# ADC_FE4PID.net
KiCad netlist of a schematic drawn in Altium Designer
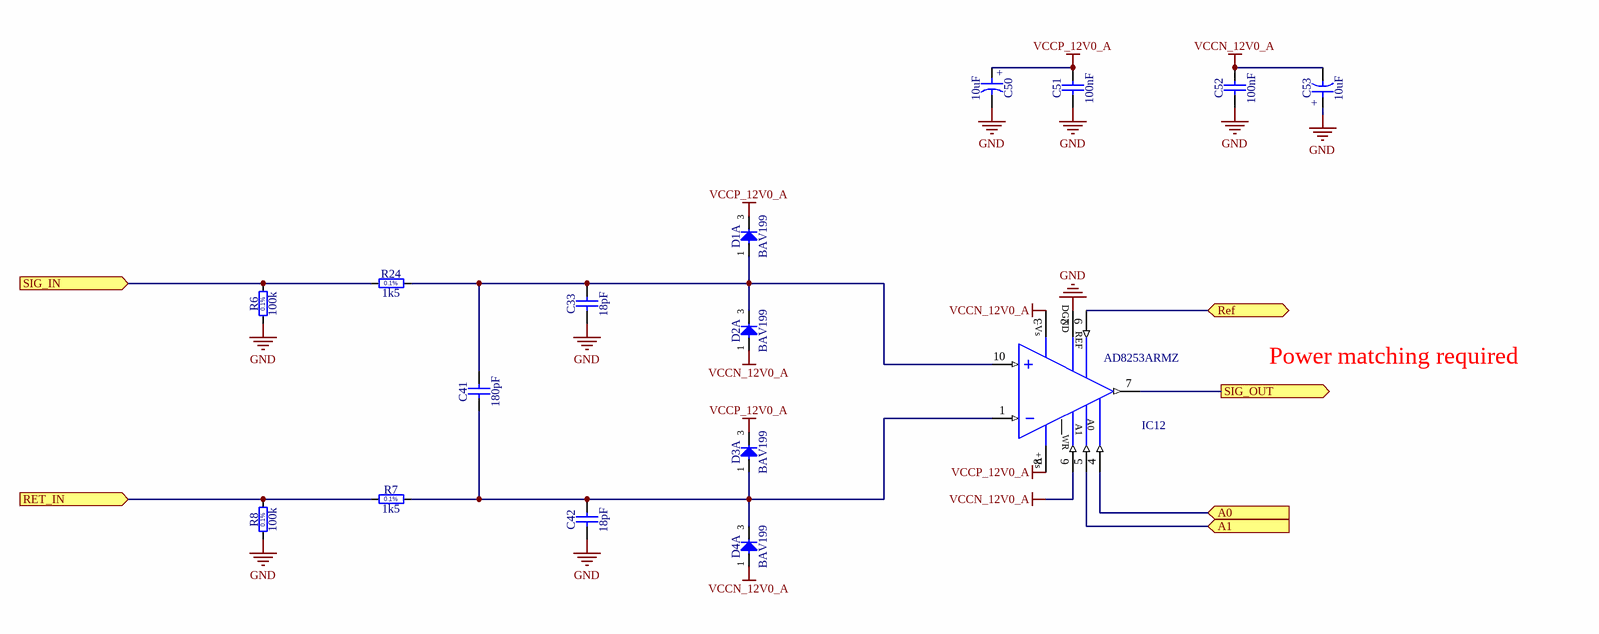
[diagram p0: ADC_FE4PID.SchDoc]

(export (version "E")
  (design (tool "Eeschema 10.0.6"))
  (components
    (comp (ref "C33")
      (value "18pF")
      (footprint "CAPC1005X55N")
      (description "Non-polarised capacitor")
      (fields
        (field (name "PART NUMBER") "CC0402_18PF_50V_5%_C0G")
        (field (name "VOLTAGE") "50V")
        (field (name "AUTHOR") "CERN DEM JLC")
      )
      (libsource (lib "Capacitors") (part "Capacitor - non polarized"))
    )
    (comp (ref "C41")
      (value "180pF")
      (footprint "CAPC1608X87N")
      (description "Non-polarised capacitor")
      (fields
        (field (name "PART NUMBER") "CC0603_180PF_50V_5%_NP0")
        (field (name "VOLTAGE") "50V")
        (field (name "AUTHOR") "CERN DEM JLC")
      )
      (libsource (lib "Capacitors") (part "Capacitor - non polarized"))
    )
    (comp (ref "C42")
      (value "18pF")
      (footprint "CAPC1005X55N")
      (description "Non-polarised capacitor")
      (fields
        (field (name "PART NUMBER") "CC0402_18PF_50V_5%_C0G")
        (field (name "VOLTAGE") "50V")
        (field (name "AUTHOR") "CERN DEM JLC")
      )
      (libsource (lib "Capacitors") (part "Capacitor - non polarized"))
    )
    (comp (ref "C50")
      (value "10uF")
      (footprint "CAPMP3216X180N")
      (description "Polarised capacitor")
      (fields
        (field (name "PART NUMBER") "CTE3216-18_10UF_10V_10%_LESR1800")
        (field (name "VOLTAGE") "10V")
        (field (name "AUTHOR") "CERN DEM JLC")
      )
      (libsource (lib "Capacitors") (part "Capacitor - polarized"))
    )
    (comp (ref "C51")
      (value "100nF")
      (footprint "CAPC1005X55N")
      (description "Non-polarised capacitor")
      (fields
        (field (name "PART NUMBER") "CC0402_100NF_16V_10%_X7R")
        (field (name "VOLTAGE") "16V")
        (field (name "AUTHOR") "CERN DEM JLC")
      )
      (libsource (lib "Capacitors") (part "Capacitor - non polarized"))
    )
    (comp (ref "C52")
      (value "100nF")
      (footprint "CAPC1005X55N")
      (description "Non-polarised capacitor")
      (fields
        (field (name "PART NUMBER") "CC0402_100NF_16V_10%_X7R")
        (field (name "VOLTAGE") "16V")
        (field (name "AUTHOR") "CERN DEM JLC")
      )
      (libsource (lib "Capacitors") (part "Capacitor - non polarized"))
    )
    (comp (ref "C53")
      (value "10uF")
      (footprint "CAPMP3216X180N")
      (description "Polarised capacitor")
      (fields
        (field (name "PART NUMBER") "CTE3216-18_10UF_10V_10%_LESR1800")
        (field (name "VOLTAGE") "10V")
        (field (name "AUTHOR") "CERN DEM JLC")
      )
      (libsource (lib "Capacitors") (part "Capacitor - polarized"))
    )
    (comp (ref "D1")
      (value "BAV199")
      (footprint "SOT95P240X110-3N")
      (description "Serial Diode")
      (fields
        (field (name "VOLTAGE") "75V")
        (field (name "POWER") "250mW")
        (field (name "AUTHOR") "CERN DEM JMW")
      )
      (libsource (lib "ICs And Semiconductors") (part "Diode x2 A1C3_A3C2"))
    )
    (comp (ref "D2")
      (value "BAV199")
      (footprint "SOT95P240X110-3N")
      (description "Serial Diode")
      (fields
        (field (name "VOLTAGE") "75V")
        (field (name "POWER") "250mW")
        (field (name "AUTHOR") "CERN DEM JMW")
      )
      (libsource (lib "ICs And Semiconductors") (part "Diode x2 A1C3_A3C2"))
    )
    (comp (ref "D3")
      (value "BAV199")
      (footprint "SOT95P240X110-3N")
      (description "Serial Diode")
      (fields
        (field (name "VOLTAGE") "75V")
        (field (name "POWER") "250mW")
        (field (name "AUTHOR") "CERN DEM JMW")
      )
      (libsource (lib "ICs And Semiconductors") (part "Diode x2 A1C3_A3C2"))
    )
    (comp (ref "D4")
      (value "BAV199")
      (footprint "SOT95P240X110-3N")
      (description "Serial Diode")
      (fields
        (field (name "VOLTAGE") "75V")
        (field (name "POWER") "250mW")
        (field (name "AUTHOR") "CERN DEM JMW")
      )
      (libsource (lib "ICs And Semiconductors") (part "Diode x2 A1C3_A3C2"))
    )
    (comp (ref "IC12")
      (value "AD8253ARMZ")
      (footprint "SOP50P490X110-10N")
      (description "10MHz, 20V/us, G= 1, 10, 100, 1000 iCMOS Programmable Gain Instrumentation Amplifier")
      (fields (field (name "MANUFACTURER") "ANALOG DEVICES") (field (name "AUTHOR") "CERN DEM JLC"))
      (libsource (lib "ICs And Semiconductors") (part "AD8253"))
    )
    (comp (ref "R6")
      (value "100k")
      (footprint "RESC1005X35N")
      (description "Resistor - 0.1%")
      (fields
        (field (name "PART NUMBER") "R0402_100K_0.1%_0.063W_25PPM")
        (field (name "POWER") "0.063W")
        (field (name "AUTHOR") "CERN DEM JMW")
      )
      (libsource (lib "Resistors") (part "Resistor - 0.1%"))
    )
    (comp (ref "R7")
      (value "1k5")
      (footprint "RESC1608X55N")
      (description "Resistor - 0.1%")
      (fields
        (field (name "PART NUMBER") "R0603_1K5_0.1%_0.063W_10PPM")
        (field (name "POWER") "0.063W")
        (field (name "AUTHOR") "CERN DEM JLC")
      )
      (libsource (lib "Resistors") (part "Resistor - 0.1%"))
    )
    (comp (ref "R8")
      (value "100k")
      (footprint "RESC1005X35N")
      (description "Resistor - 0.1%")
      (fields
        (field (name "PART NUMBER") "R0402_100K_0.1%_0.063W_25PPM")
        (field (name "POWER") "0.063W")
        (field (name "AUTHOR") "CERN DEM JMW")
      )
      (libsource (lib "Resistors") (part "Resistor - 0.1%"))
    )
    (comp (ref "R24")
      (value "1k5")
      (footprint "RESC1608X55N")
      (description "Resistor - 0.1%")
      (fields
        (field (name "PART NUMBER") "R0603_1K5_0.1%_0.063W_10PPM")
        (field (name "POWER") "0.063W")
        (field (name "AUTHOR") "CERN DEM JLC")
      )
      (libsource (lib "Resistors") (part "Resistor - 0.1%"))
    )
  )
  (nets
    (net (code "1") (name "/A0") (class "Default")
      (node (ref "IC12") (pin "4") (pinfunction "A0_4") (pintype "input"))
    )
    (net (code "2") (name "/A1") (class "Default")
      (node (ref "IC12") (pin "5") (pinfunction "A1_5") (pintype "input"))
    )
    (net (code "3") (name "/RET_IN") (class "Default")
      (node (ref "R7") (pin "1") (pinfunction "1_1") (pintype "passive"))
      (node (ref "R8") (pin "2") (pinfunction "2_2") (pintype "passive"))
    )
    (net (code "4") (name "/Ref") (class "Default")
      (node (ref "IC12") (pin "9") (pinfunction "REF_9") (pintype "input"))
    )
    (net (code "5") (name "/SIG_IN") (class "Default")
      (node (ref "R24") (pin "1") (pinfunction "1_1") (pintype "passive"))
      (node (ref "R6") (pin "2") (pinfunction "2_2") (pintype "passive"))
    )
    (net (code "6") (name "/SIG_OUT") (class "Default")
      (node (ref "IC12") (pin "7") (pinfunction "OUT_7") (pintype "output"))
    )
    (net (code "7") (name "GND") (class "Default")
      (node (ref "C33") (pin "1") (pinfunction "1_1") (pintype "passive"))
      (node (ref "C42") (pin "1") (pinfunction "1_1") (pintype "passive"))
      (node (ref "C50") (pin "2") (pinfunction "2_2") (pintype "passive"))
      (node (ref "C51") (pin "1") (pinfunction "1_1") (pintype "passive"))
      (node (ref "C52") (pin "1") (pinfunction "1_1") (pintype "passive"))
      (node (ref "C53") (pin "1") (pinfunction "1_1") (pintype "passive"))
      (node (ref "IC12") (pin "2") (pinfunction "DGND_2") (pintype "power_in"))
      (node (ref "R6") (pin "1") (pinfunction "1_1") (pintype "passive"))
      (node (ref "R8") (pin "1") (pinfunction "1_1") (pintype "passive"))
    )
    (net (code "8") (name "Net-(D1A-A)") (class "Default")
      (node (ref "C33") (pin "2") (pinfunction "2_2") (pintype "passive"))
      (node (ref "C41") (pin "2") (pinfunction "2_2") (pintype "passive"))
      (node (ref "D1") (pin "1") (pinfunction "A_1") (pintype "passive"))
      (node (ref "D2") (pin "3") (pinfunction "COMAC_3") (pintype "passive"))
      (node (ref "IC12") (pin "10") (pinfunction "+IN_10") (pintype "input"))
      (node (ref "R24") (pin "2") (pinfunction "2_2") (pintype "passive"))
    )
    (net (code "9") (name "Net-(D3A-A)") (class "Default")
      (node (ref "C41") (pin "1") (pinfunction "1_1") (pintype "passive"))
      (node (ref "C42") (pin "2") (pinfunction "2_2") (pintype "passive"))
      (node (ref "D3") (pin "1") (pinfunction "A_1") (pintype "passive"))
      (node (ref "D4") (pin "3") (pinfunction "COMAC_3") (pintype "passive"))
      (node (ref "IC12") (pin "1") (pinfunction "-IN_1") (pintype "input"))
      (node (ref "R7") (pin "2") (pinfunction "2_2") (pintype "passive"))
    )
    (net (code "10") (name "VCCN_12V0_A") (class "Default")
      (node (ref "C52") (pin "2") (pinfunction "2_2") (pintype "passive"))
      (node (ref "C53") (pin "2") (pinfunction "2_2") (pintype "passive"))
      (node (ref "D2") (pin "1") (pinfunction "A_1") (pintype "passive"))
      (node (ref "D4") (pin "1") (pinfunction "A_1") (pintype "passive"))
      (node (ref "IC12") (pin "3") (pinfunction "-VS_3") (pintype "power_in"))
      (node (ref "IC12") (pin "6") (pinfunction "~{WR}_6") (pintype "input"))
    )
    (net (code "11") (name "VCCP_12V0_A") (class "Default")
      (node (ref "C50") (pin "1") (pinfunction "1_1") (pintype "passive"))
      (node (ref "C51") (pin "2") (pinfunction "2_2") (pintype "passive"))
      (node (ref "D1") (pin "3") (pinfunction "COMAC_3") (pintype "passive"))
      (node (ref "D3") (pin "3") (pinfunction "COMAC_3") (pintype "passive"))
      (node (ref "IC12") (pin "8") (pinfunction "+VS_8") (pintype "power_in"))
    )
  )
)
